# TVHR-PFG01.net
KiCad netlist of a schematic drawn in EAGLE
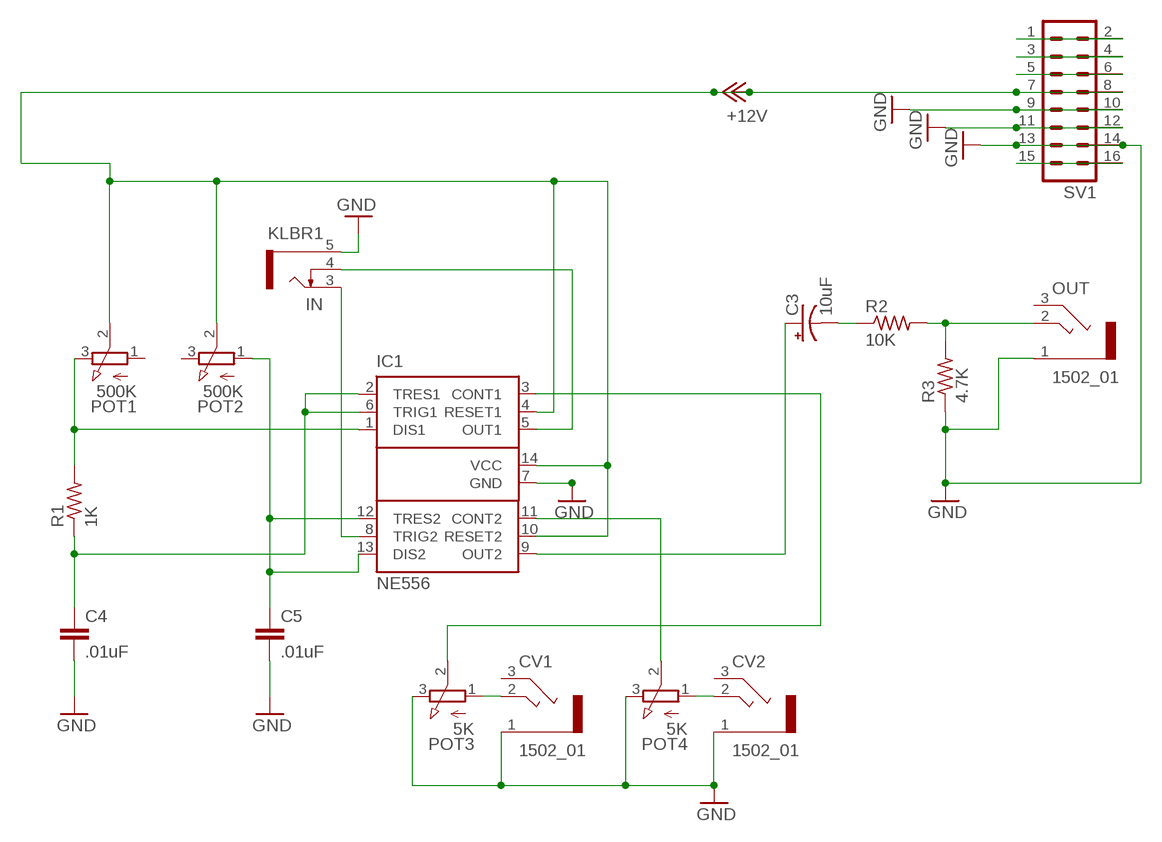
[diagram p0: schematic, sheet 1]

(export (version "E")
  (design (tool "Eeschema 10.0.6"))
  (components
    (comp (ref "C3")
      (value "10uF")
      (footprint "eagle-import:E2,5-5")
      (libsource (lib "eagle-import") (part "CPOL-USE2.5-5"))
    )
    (comp (ref "C4")
      (value ".01uF")
      (footprint "eagle-import:C2.5-3")
      (libsource (lib "eagle-import") (part "C2,5-3"))
    )
    (comp (ref "C5")
      (value ".01uF")
      (footprint "eagle-import:C2.5-3")
      (libsource (lib "eagle-import") (part "C2,5-3"))
    )
    (comp (ref "CV1")
      (value "1502_01")
      (footprint "eagle-import:1502_01")
      (libsource (lib "eagle-import") (part "1502_01"))
    )
    (comp (ref "CV2")
      (value "1502_01")
      (footprint "eagle-import:1502_01")
      (libsource (lib "eagle-import") (part "1502_01"))
    )
    (comp (ref "IC1")
      (value "NE556")
      (footprint "eagle-import:DIL14")
      (libsource (lib "eagle-import") (part "NE556"))
    )
    (comp (ref "IN")
      (value "KLBR1")
      (footprint "eagle-import:KLBR1")
      (fields (field (name "MPN") "KLBR 1"))
      (libsource (lib "eagle-import") (part "KLBR?1"))
    )
    (comp (ref "OUT")
      (value "1502_01")
      (footprint "eagle-import:1502_01")
      (libsource (lib "eagle-import") (part "1502_01"))
    )
    (comp (ref "POT1")
      (value "500K")
      (footprint "eagle-import:3RP_1610N")
      (libsource (lib "eagle-import") (part "3RP/1610N"))
    )
    (comp (ref "POT2")
      (value "500K")
      (footprint "eagle-import:3RP_1610N")
      (libsource (lib "eagle-import") (part "3RP/1610N"))
    )
    (comp (ref "POT3")
      (value "5K")
      (footprint "eagle-import:3RP_1610N")
      (libsource (lib "eagle-import") (part "3RP/1610N"))
    )
    (comp (ref "POT4")
      (value "5K")
      (footprint "eagle-import:3RP_1610N")
      (libsource (lib "eagle-import") (part "3RP/1610N"))
    )
    (comp (ref "R1")
      (value "1K")
      (footprint "eagle-import:0204_7")
      (libsource (lib "eagle-import") (part "R-US_0204/7"))
    )
    (comp (ref "R2")
      (value "10K")
      (footprint "eagle-import:0204_7")
      (libsource (lib "eagle-import") (part "R-US_0204/7"))
    )
    (comp (ref "R3")
      (value "4.7K")
      (footprint "eagle-import:0204_7")
      (libsource (lib "eagle-import") (part "R-US_0204/7"))
    )
    (comp (ref "SV1")
      (value "MA08-2")
      (footprint "eagle-import:MA08-2")
      (libsource (lib "eagle-import") (part "MA08-2"))
    )
  )
  (nets
    (net (code "1") (name "+12V") (class "Default")
      (node (ref "IC1") (pin "10") (pinfunction "RESET2_10") (pintype "input"))
      (node (ref "IC1") (pin "14") (pinfunction "VCC_14") (pintype "power_in"))
      (node (ref "IC1") (pin "4") (pinfunction "RESET1_4") (pintype "input"))
      (node (ref "POT1") (pin "2") (pinfunction "S_2") (pintype "passive"))
      (node (ref "POT2") (pin "2") (pinfunction "S_2") (pintype "passive"))
      (node (ref "SV1") (pin "7") (pinfunction "7_7") (pintype "passive"))
      (node (ref "SV1") (pin "8") (pinfunction "8_8") (pintype "passive"))
    )
    (net (code "2") (name "GND") (class "Default")
      (node (ref "C4") (pin "2") (pinfunction "2_2") (pintype "passive"))
      (node (ref "C5") (pin "2") (pinfunction "2_2") (pintype "passive"))
      (node (ref "CV1") (pin "1") (pinfunction "1_1") (pintype "passive"))
      (node (ref "CV2") (pin "1") (pinfunction "1_1") (pintype "passive"))
      (node (ref "IC1") (pin "7") (pinfunction "GND_7") (pintype "power_in"))
      (node (ref "IN") (pin "5") (pinfunction "5_5") (pintype "passive"))
      (node (ref "OUT") (pin "1") (pinfunction "1_1") (pintype "passive"))
      (node (ref "POT3") (pin "3") (pinfunction "E_3") (pintype "passive"))
      (node (ref "POT4") (pin "3") (pinfunction "E_3") (pintype "passive"))
      (node (ref "R3") (pin "1") (pinfunction "1_1") (pintype "passive"))
      (node (ref "SV1") (pin "10") (pinfunction "10_10") (pintype "passive"))
      (node (ref "SV1") (pin "11") (pinfunction "11_11") (pintype "passive"))
      (node (ref "SV1") (pin "12") (pinfunction "12_12") (pintype "passive"))
      (node (ref "SV1") (pin "13") (pinfunction "13_13") (pintype "passive"))
      (node (ref "SV1") (pin "14") (pinfunction "14_14") (pintype "passive"))
      (node (ref "SV1") (pin "9") (pinfunction "9_9") (pintype "passive"))
    )
    (net (code "3") (name "Net-(C3-Pad-)") (class "Default")
      (node (ref "C3") (pin "-") (pinfunction "-_-") (pintype "passive"))
      (node (ref "R2") (pin "1") (pinfunction "1_1") (pintype "passive"))
    )
    (net (code "4") (name "Net-(CV1-3)") (class "Default")
      (node (ref "CV1") (pin "2") (pinfunction "3_2") (pintype "passive"))
      (node (ref "POT3") (pin "1") (pinfunction "A_1") (pintype "passive"))
    )
    (net (code "5") (name "Net-(CV2-3)") (class "Default")
      (node (ref "CV2") (pin "2") (pinfunction "3_2") (pintype "passive"))
      (node (ref "POT4") (pin "1") (pinfunction "A_1") (pintype "passive"))
    )
    (net (code "6") (name "Net-(IC1-CONT1)") (class "Default")
      (node (ref "IC1") (pin "3") (pinfunction "CONT1_3") (pintype "input"))
      (node (ref "POT3") (pin "2") (pinfunction "S_2") (pintype "passive"))
    )
    (net (code "7") (name "Net-(IC1-CONT2)") (class "Default")
      (node (ref "IC1") (pin "11") (pinfunction "CONT2_11") (pintype "input"))
      (node (ref "POT4") (pin "2") (pinfunction "S_2") (pintype "passive"))
    )
    (net (code "8") (name "Net-(IC1-DIS1)") (class "Default")
      (node (ref "IC1") (pin "1") (pinfunction "DIS1_1") (pintype "input"))
      (node (ref "POT1") (pin "3") (pinfunction "E_3") (pintype "passive"))
      (node (ref "R1") (pin "2") (pinfunction "2_2") (pintype "passive"))
    )
    (net (code "9") (name "Net-(IC1-DIS2)") (class "Default")
      (node (ref "C5") (pin "1") (pinfunction "1_1") (pintype "passive"))
      (node (ref "IC1") (pin "12") (pinfunction "TRES2_12") (pintype "input"))
      (node (ref "IC1") (pin "13") (pinfunction "DIS2_13") (pintype "input"))
      (node (ref "POT2") (pin "1") (pinfunction "A_1") (pintype "passive"))
    )
    (net (code "10") (name "Net-(IC1-OUT1)") (class "Default")
      (node (ref "IC1") (pin "5") (pinfunction "OUT1_5") (pintype "output"))
      (node (ref "IN") (pin "4") (pinfunction "4_4") (pintype "passive"))
    )
    (net (code "11") (name "Net-(IC1-OUT2)") (class "Default")
      (node (ref "C3") (pin "+") (pinfunction "+_+") (pintype "passive"))
      (node (ref "IC1") (pin "9") (pinfunction "OUT2_9") (pintype "output"))
    )
    (net (code "12") (name "Net-(IC1-TRES1)") (class "Default")
      (node (ref "C4") (pin "1") (pinfunction "1_1") (pintype "passive"))
      (node (ref "IC1") (pin "2") (pinfunction "TRES1_2") (pintype "input"))
      (node (ref "IC1") (pin "6") (pinfunction "TRIG1_6") (pintype "input"))
      (node (ref "R1") (pin "1") (pinfunction "1_1") (pintype "passive"))
    )
    (net (code "13") (name "Net-(IC1-TRIG2)") (class "Default")
      (node (ref "IC1") (pin "8") (pinfunction "TRIG2_8") (pintype "input"))
      (node (ref "IN") (pin "3") (pinfunction "3_3") (pintype "passive"))
    )
    (net (code "14") (name "Net-(OUT-3)") (class "Default")
      (node (ref "OUT") (pin "2") (pinfunction "3_2") (pintype "passive"))
      (node (ref "R2") (pin "2") (pinfunction "2_2") (pintype "passive"))
      (node (ref "R3") (pin "2") (pinfunction "2_2") (pintype "passive"))
    )
    (net (code "15") (name "Net-(SV1-Pad1)") (class "Default")
      (node (ref "SV1") (pin "1") (pinfunction "1_1") (pintype "passive"))
      (node (ref "SV1") (pin "2") (pinfunction "2_2") (pintype "passive"))
    )
    (net (code "16") (name "Net-(SV1-Pad3)") (class "Default")
      (node (ref "SV1") (pin "3") (pinfunction "3_3") (pintype "passive"))
      (node (ref "SV1") (pin "4") (pinfunction "4_4") (pintype "passive"))
    )
    (net (code "17") (name "Net-(SV1-Pad5)") (class "Default")
      (node (ref "SV1") (pin "5") (pinfunction "5_5") (pintype "passive"))
      (node (ref "SV1") (pin "6") (pinfunction "6_6") (pintype "passive"))
    )
    (net (code "18") (name "Net-(SV1-Pad15)") (class "Default")
      (node (ref "SV1") (pin "15") (pinfunction "15_15") (pintype "passive"))
      (node (ref "SV1") (pin "16") (pinfunction "16_16") (pintype "passive"))
    )
    (net (code "19") (name "unconnected-(CV1-2-Pad3)") (class "Default")
      (node (ref "CV1") (pin "3") (pinfunction "2_3") (pintype "passive"))
    )
    (net (code "20") (name "unconnected-(CV2-2-Pad3)") (class "Default")
      (node (ref "CV2") (pin "3") (pinfunction "2_3") (pintype "passive"))
    )
    (net (code "21") (name "unconnected-(OUT-2-Pad3)") (class "Default")
      (node (ref "OUT") (pin "3") (pinfunction "2_3") (pintype "passive"))
    )
    (net (code "22") (name "unconnected-(POT1-A-Pad1)") (class "Default")
      (node (ref "POT1") (pin "1") (pinfunction "A_1") (pintype "passive"))
    )
    (net (code "23") (name "unconnected-(POT2-E-Pad3)") (class "Default")
      (node (ref "POT2") (pin "3") (pinfunction "E_3") (pintype "passive"))
    )
  )
)
